# dsky_md_2_1v.net
KiCad netlist of a schematic drawn in EAGLE
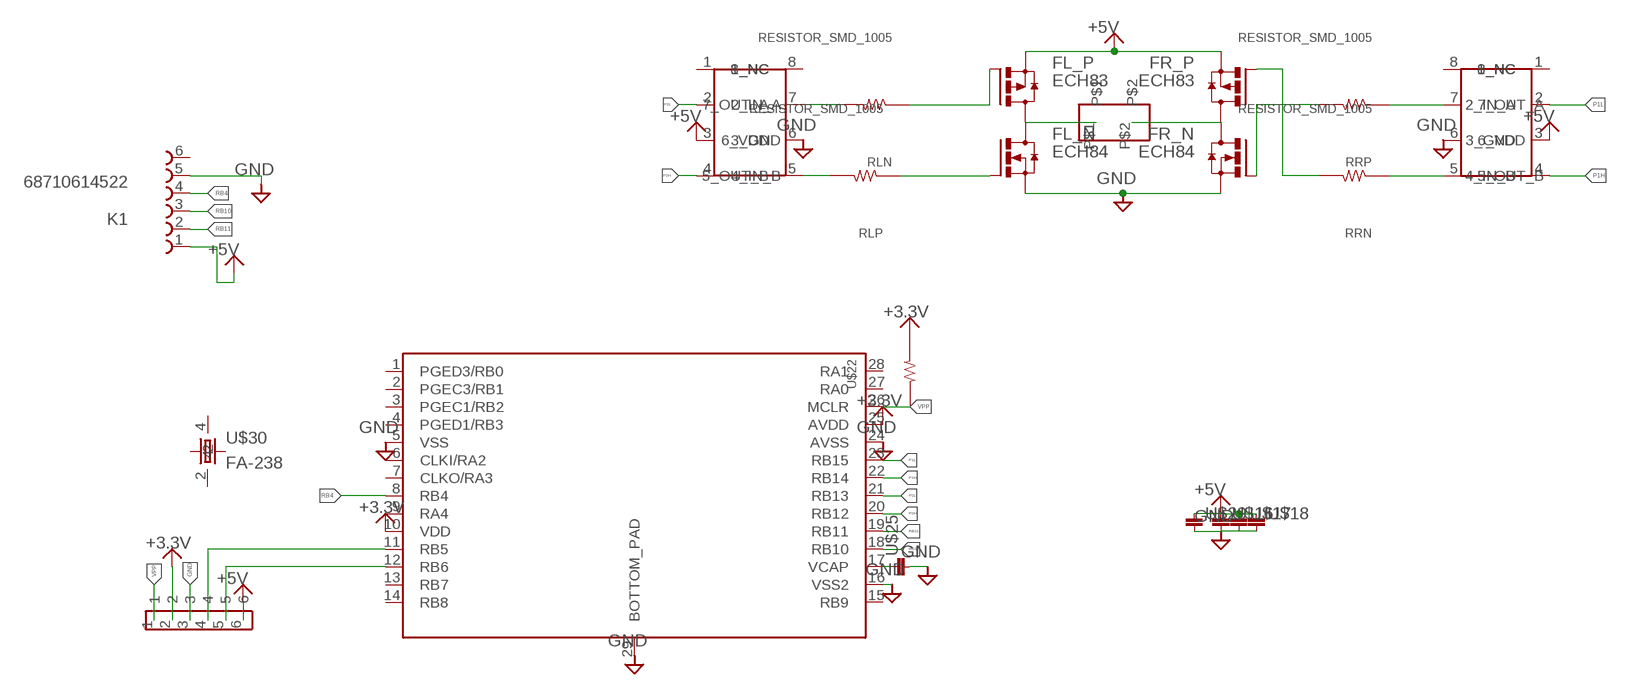
[diagram p0: schematic, sheet 1]

(export (version "E")
  (design (tool "Eeschema 10.0.6"))
  (components
    (comp (ref "FL_N")
      (value "ECH84")
      (footprint "eagle-import:ECH8")
      (libsource (lib "eagle-import") (part "ECH84"))
    )
    (comp (ref "FL_P")
      (value "ECH83")
      (footprint "eagle-import:ECH8")
      (libsource (lib "eagle-import") (part "ECH83"))
    )
    (comp (ref "FR_N")
      (value "ECH84")
      (footprint "eagle-import:ECH8")
      (libsource (lib "eagle-import") (part "ECH84"))
    )
    (comp (ref "FR_P")
      (value "ECH83")
      (footprint "eagle-import:ECH8")
      (libsource (lib "eagle-import") (part "ECH83"))
    )
    (comp (ref "IC_L")
      (value "TC1427COA")
      (footprint "eagle-import:SOIC8")
      (libsource (lib "eagle-import") (part "TC1427COA"))
    )
    (comp (ref "IC_R")
      (value "TC1427COA")
      (footprint "eagle-import:SOIC8")
      (libsource (lib "eagle-import") (part "TC1427COA"))
    )
    (comp (ref "K1")
      (value "68710614522")
      (footprint "eagle-import:68710614522")
      (libsource (lib "eagle-import") (part "68710614522"))
    )
    (comp (ref "RLN")
      (value "RESISTOR_SMD_1005")
      (footprint "eagle-import:1005")
      (libsource (lib "eagle-import") (part "RESISTOR_SMD_1005"))
    )
    (comp (ref "RLP")
      (value "RESISTOR_SMD_1005")
      (footprint "eagle-import:1005")
      (libsource (lib "eagle-import") (part "RESISTOR_SMD_1005"))
    )
    (comp (ref "RRN")
      (value "RESISTOR_SMD_1005")
      (footprint "eagle-import:1005")
      (libsource (lib "eagle-import") (part "RESISTOR_SMD_1005"))
    )
    (comp (ref "RRP")
      (value "RESISTOR_SMD_1005")
      (footprint "eagle-import:1005")
      (libsource (lib "eagle-import") (part "RESISTOR_SMD_1005"))
    )
    (comp (ref "U$3")
      (value "PIN_HEADER_2")
      (footprint "eagle-import:PIN_HEADER_2S")
      (libsource (lib "eagle-import") (part "PIN_HEADER_2"))
    )
    (comp (ref "U$5")
      (value "DSPIC33EP32MC202")
      (footprint "eagle-import:QFN-S28_6X6MC")
      (libsource (lib "eagle-import") (part "DSPIC33EP32MC202"))
    )
    (comp (ref "U$6")
      (value "PIN_HEADER_HALF_6")
      (footprint "eagle-import:PIN_HEADER_HALF_6")
      (libsource (lib "eagle-import") (part "PIN_HEADER_HALF_6"))
    )
    (comp (ref "U$16")
      (value "1608")
      (footprint "eagle-import:1608")
      (libsource (lib "eagle-import") (part "1608"))
    )
    (comp (ref "U$17")
      (value "1608")
      (footprint "eagle-import:1608")
      (libsource (lib "eagle-import") (part "1608"))
    )
    (comp (ref "U$18")
      (value "1608")
      (footprint "eagle-import:1608")
      (libsource (lib "eagle-import") (part "1608"))
    )
    (comp (ref "U$22")
      (value "RESISTOR__SMD")
      (footprint "eagle-import:1608")
      (libsource (lib "eagle-import") (part "RESISTOR__SMD"))
    )
    (comp (ref "U$25")
      (value "1608")
      (footprint "eagle-import:1608")
      (libsource (lib "eagle-import") (part "1608"))
    )
    (comp (ref "U$29")
      (value "2012")
      (footprint "eagle-import:2012")
      (libsource (lib "eagle-import") (part "2012"))
    )
    (comp (ref "U$30")
      (value "FA-238")
      (footprint "eagle-import:FA-238")
      (libsource (lib "eagle-import") (part "FA-238"))
    )
  )
  (nets
    (net (code "1") (name "+3.3V") (class "Default")
      (node (ref "U$22") (pin "2") (pinfunction "P$2_2") (pintype "passive"))
      (node (ref "U$5") (pin "10") (pinfunction "VDD_10") (pintype "bidirectional"))
      (node (ref "U$5") (pin "25") (pinfunction "AVDD_25") (pintype "bidirectional"))
      (node (ref "U$6") (pin "2") (pinfunction "2_2") (pintype "bidirectional"))
    )
    (net (code "2") (name "+5V") (class "Default")
      (node (ref "FL_P") (pin "1") (pinfunction "S_1") (pintype "passive"))
      (node (ref "FL_P") (pin "2") (pinfunction "S_2") (pintype "passive"))
      (node (ref "FL_P") (pin "3") (pinfunction "S_3") (pintype "passive"))
      (node (ref "FR_P") (pin "1") (pinfunction "S_1") (pintype "passive"))
      (node (ref "FR_P") (pin "2") (pinfunction "S_2") (pintype "passive"))
      (node (ref "FR_P") (pin "3") (pinfunction "S_3") (pintype "passive"))
      (node (ref "IC_L") (pin "3") (pinfunction "3_GND_3") (pintype "bidirectional"))
      (node (ref "IC_R") (pin "3") (pinfunction "3_GND_3") (pintype "bidirectional"))
      (node (ref "K1") (pin "1") (pinfunction "1_1") (pintype "passive"))
      (node (ref "U$16") (pin "P$1") (pinfunction "1_P$1") (pintype "passive"))
      (node (ref "U$17") (pin "P$1") (pinfunction "1_P$1") (pintype "passive"))
      (node (ref "U$18") (pin "P$1") (pinfunction "1_P$1") (pintype "passive"))
      (node (ref "U$29") (pin "1") (pinfunction "1_1") (pintype "passive"))
      (node (ref "U$6") (pin "6") (pinfunction "6_6") (pintype "bidirectional"))
    )
    (net (code "3") (name "GND") (class "Default")
      (node (ref "FL_N") (pin "1") (pinfunction "S_1") (pintype "passive"))
      (node (ref "FL_N") (pin "2") (pinfunction "S_2") (pintype "passive"))
      (node (ref "FL_N") (pin "3") (pinfunction "S_3") (pintype "passive"))
      (node (ref "FR_N") (pin "1") (pinfunction "S_1") (pintype "passive"))
      (node (ref "FR_N") (pin "2") (pinfunction "S_2") (pintype "passive"))
      (node (ref "FR_N") (pin "3") (pinfunction "S_3") (pintype "passive"))
      (node (ref "IC_L") (pin "6") (pinfunction "6_VDD_6") (pintype "bidirectional"))
      (node (ref "IC_R") (pin "6") (pinfunction "6_VDD_6") (pintype "bidirectional"))
      (node (ref "K1") (pin "5") (pinfunction "5_5") (pintype "passive"))
      (node (ref "U$16") (pin "P$2") (pinfunction "2_P$2") (pintype "passive"))
      (node (ref "U$17") (pin "P$2") (pinfunction "2_P$2") (pintype "passive"))
      (node (ref "U$18") (pin "P$2") (pinfunction "2_P$2") (pintype "passive"))
      (node (ref "U$25") (pin "P$2") (pinfunction "2_P$2") (pintype "passive"))
      (node (ref "U$29") (pin "2") (pinfunction "2_2") (pintype "passive"))
      (node (ref "U$5") (pin "16") (pinfunction "VSS2_16") (pintype "power_in"))
      (node (ref "U$5") (pin "24") (pinfunction "AVSS_24") (pintype "bidirectional"))
      (node (ref "U$5") (pin "29") (pinfunction "BOTTOM_PAD_29") (pintype "bidirectional"))
      (node (ref "U$5") (pin "5") (pinfunction "VSS_5") (pintype "power_in"))
      (node (ref "U$6") (pin "3") (pinfunction "3_3") (pintype "bidirectional"))
    )
    (net (code "4") (name "Net-(FL_N-D-Pad5)") (class "Default")
      (node (ref "FL_N") (pin "5") (pinfunction "D_5") (pintype "passive"))
      (node (ref "FL_N") (pin "6") (pinfunction "D_6") (pintype "passive"))
      (node (ref "FL_N") (pin "7") (pinfunction "D_7") (pintype "passive"))
      (node (ref "FL_N") (pin "8") (pinfunction "D_8") (pintype "passive"))
      (node (ref "FL_P") (pin "5") (pinfunction "D_5") (pintype "passive"))
      (node (ref "FL_P") (pin "6") (pinfunction "D_6") (pintype "passive"))
      (node (ref "FL_P") (pin "7") (pinfunction "D_7") (pintype "passive"))
      (node (ref "FL_P") (pin "8") (pinfunction "D_8") (pintype "passive"))
      (node (ref "U$3") (pin "P$1") (pinfunction "P$1_P$1") (pintype "bidirectional"))
    )
    (net (code "5") (name "Net-(FL_N-G)") (class "Default")
      (node (ref "FL_N") (pin "4") (pinfunction "G_4") (pintype "passive"))
      (node (ref "RLP") (pin "1") (pinfunction "P$1_1") (pintype "passive"))
    )
    (net (code "6") (name "Net-(FL_P-G)") (class "Default")
      (node (ref "FL_P") (pin "4") (pinfunction "G_4") (pintype "passive"))
      (node (ref "RLN") (pin "1") (pinfunction "P$1_1") (pintype "passive"))
    )
    (net (code "7") (name "Net-(FR_N-D-Pad5)") (class "Default")
      (node (ref "FR_N") (pin "5") (pinfunction "D_5") (pintype "passive"))
      (node (ref "FR_N") (pin "6") (pinfunction "D_6") (pintype "passive"))
      (node (ref "FR_N") (pin "7") (pinfunction "D_7") (pintype "passive"))
      (node (ref "FR_N") (pin "8") (pinfunction "D_8") (pintype "passive"))
      (node (ref "FR_P") (pin "5") (pinfunction "D_5") (pintype "passive"))
      (node (ref "FR_P") (pin "6") (pinfunction "D_6") (pintype "passive"))
      (node (ref "FR_P") (pin "7") (pinfunction "D_7") (pintype "passive"))
      (node (ref "FR_P") (pin "8") (pinfunction "D_8") (pintype "passive"))
      (node (ref "U$3") (pin "P$2") (pinfunction "P$2_P$2") (pintype "bidirectional"))
    )
    (net (code "8") (name "Net-(FR_N-G)") (class "Default")
      (node (ref "FR_N") (pin "4") (pinfunction "G_4") (pintype "passive"))
      (node (ref "RRP") (pin "2") (pinfunction "P$2_2") (pintype "passive"))
    )
    (net (code "9") (name "Net-(FR_P-G)") (class "Default")
      (node (ref "FR_P") (pin "4") (pinfunction "G_4") (pintype "passive"))
      (node (ref "RRN") (pin "2") (pinfunction "P$2_2") (pintype "passive"))
    )
    (net (code "10") (name "Net-(IC_L-5_OUT_B)") (class "Default")
      (node (ref "IC_L") (pin "5") (pinfunction "5_OUT_B_5") (pintype "bidirectional"))
      (node (ref "RLP") (pin "2") (pinfunction "P$2_2") (pintype "passive"))
    )
    (net (code "11") (name "Net-(IC_L-7_OUT_A)") (class "Default")
      (node (ref "IC_L") (pin "7") (pinfunction "7_OUT_A_7") (pintype "bidirectional"))
      (node (ref "RLN") (pin "2") (pinfunction "P$2_2") (pintype "passive"))
    )
    (net (code "12") (name "Net-(IC_R-5_OUT_B)") (class "Default")
      (node (ref "IC_R") (pin "5") (pinfunction "5_OUT_B_5") (pintype "bidirectional"))
      (node (ref "RRN") (pin "1") (pinfunction "P$1_1") (pintype "passive"))
    )
    (net (code "13") (name "Net-(IC_R-7_OUT_A)") (class "Default")
      (node (ref "IC_R") (pin "7") (pinfunction "7_OUT_A_7") (pintype "bidirectional"))
      (node (ref "RRP") (pin "1") (pinfunction "P$1_1") (pintype "passive"))
    )
    (net (code "14") (name "Net-(U$5-RB5)") (class "Default")
      (node (ref "U$5") (pin "11") (pinfunction "RB5_11") (pintype "bidirectional"))
      (node (ref "U$6") (pin "4") (pinfunction "4_4") (pintype "bidirectional"))
    )
    (net (code "15") (name "Net-(U$5-RB6)") (class "Default")
      (node (ref "U$5") (pin "12") (pinfunction "RB6_12") (pintype "bidirectional"))
      (node (ref "U$6") (pin "5") (pinfunction "5_5") (pintype "bidirectional"))
    )
    (net (code "16") (name "Net-(U$25-1)") (class "Default")
      (node (ref "U$25") (pin "P$1") (pinfunction "1_P$1") (pintype "passive"))
      (node (ref "U$5") (pin "17") (pinfunction "VCAP_17") (pintype "bidirectional"))
    )
    (net (code "17") (name "P1H") (class "Default")
      (node (ref "IC_R") (pin "4") (pinfunction "4_IN_B_4") (pintype "bidirectional"))
      (node (ref "U$5") (pin "22") (pinfunction "RB14_22") (pintype "bidirectional"))
    )
    (net (code "18") (name "P1L") (class "Default")
      (node (ref "IC_R") (pin "2") (pinfunction "2_IN_A_2") (pintype "bidirectional"))
      (node (ref "U$5") (pin "23") (pinfunction "RB15_23") (pintype "bidirectional"))
    )
    (net (code "19") (name "P2H") (class "Default")
      (node (ref "IC_L") (pin "4") (pinfunction "4_IN_B_4") (pintype "bidirectional"))
      (node (ref "U$5") (pin "20") (pinfunction "RB12_20") (pintype "bidirectional"))
    )
    (net (code "20") (name "P2L") (class "Default")
      (node (ref "IC_L") (pin "2") (pinfunction "2_IN_A_2") (pintype "bidirectional"))
      (node (ref "U$5") (pin "21") (pinfunction "RB13_21") (pintype "bidirectional"))
    )
    (net (code "21") (name "RB4") (class "Default")
      (node (ref "K1") (pin "4") (pinfunction "4_4") (pintype "passive"))
      (node (ref "U$5") (pin "8") (pinfunction "RB4_8") (pintype "bidirectional"))
    )
    (net (code "22") (name "RB10") (class "Default")
      (node (ref "K1") (pin "3") (pinfunction "3_3") (pintype "passive"))
      (node (ref "U$5") (pin "18") (pinfunction "RB10_18") (pintype "bidirectional"))
    )
    (net (code "23") (name "RB11") (class "Default")
      (node (ref "K1") (pin "2") (pinfunction "2_2") (pintype "passive"))
      (node (ref "U$5") (pin "19") (pinfunction "RB11_19") (pintype "bidirectional"))
    )
    (net (code "24") (name "VPP") (class "Default")
      (node (ref "U$22") (pin "1") (pinfunction "P$1_1") (pintype "passive"))
      (node (ref "U$5") (pin "26") (pinfunction "MCLR_26") (pintype "bidirectional"))
      (node (ref "U$6") (pin "1") (pinfunction "1_1") (pintype "bidirectional"))
    )
    (net (code "25") (name "unconnected-(IC_L-1_NC-Pad1)") (class "Default")
      (node (ref "IC_L") (pin "1") (pinfunction "1_NC_1") (pintype "bidirectional"))
    )
    (net (code "26") (name "unconnected-(IC_L-8_NC-Pad8)") (class "Default")
      (node (ref "IC_L") (pin "8") (pinfunction "8_NC_8") (pintype "bidirectional"))
    )
    (net (code "27") (name "unconnected-(IC_R-1_NC-Pad1)") (class "Default")
      (node (ref "IC_R") (pin "1") (pinfunction "1_NC_1") (pintype "bidirectional"))
    )
    (net (code "28") (name "unconnected-(IC_R-8_NC-Pad8)") (class "Default")
      (node (ref "IC_R") (pin "8") (pinfunction "8_NC_8") (pintype "bidirectional"))
    )
    (net (code "29") (name "unconnected-(K1-Pad6)") (class "Default")
      (node (ref "K1") (pin "6") (pinfunction "6_6") (pintype "passive"))
    )
    (net (code "30") (name "unconnected-(U$5-CLKI{slash}RA2-Pad6)") (class "Default")
      (node (ref "U$5") (pin "6") (pinfunction "CLKI/RA2_6") (pintype "bidirectional"))
    )
    (net (code "31") (name "unconnected-(U$5-CLKO{slash}RA3-Pad7)") (class "Default")
      (node (ref "U$5") (pin "7") (pinfunction "CLKO/RA3_7") (pintype "bidirectional"))
    )
    (net (code "32") (name "unconnected-(U$5-PGEC1{slash}RB2-Pad3)") (class "Default")
      (node (ref "U$5") (pin "3") (pinfunction "PGEC1/RB2_3") (pintype "bidirectional"))
    )
    (net (code "33") (name "unconnected-(U$5-PGEC3{slash}RB1-Pad2)") (class "Default")
      (node (ref "U$5") (pin "2") (pinfunction "PGEC3/RB1_2") (pintype "bidirectional"))
    )
    (net (code "34") (name "unconnected-(U$5-PGED1{slash}RB3-Pad4)") (class "Default")
      (node (ref "U$5") (pin "4") (pinfunction "PGED1/RB3_4") (pintype "bidirectional"))
    )
    (net (code "35") (name "unconnected-(U$5-PGED3{slash}RB0-Pad1)") (class "Default")
      (node (ref "U$5") (pin "1") (pinfunction "PGED3/RB0_1") (pintype "bidirectional"))
    )
    (net (code "36") (name "unconnected-(U$5-RA0-Pad27)") (class "Default")
      (node (ref "U$5") (pin "27") (pinfunction "RA0_27") (pintype "bidirectional"))
    )
    (net (code "37") (name "unconnected-(U$5-RA1-Pad28)") (class "Default")
      (node (ref "U$5") (pin "28") (pinfunction "RA1_28") (pintype "bidirectional"))
    )
    (net (code "38") (name "unconnected-(U$5-RA4-Pad9)") (class "Default")
      (node (ref "U$5") (pin "9") (pinfunction "RA4_9") (pintype "bidirectional"))
    )
    (net (code "39") (name "unconnected-(U$5-RB7-Pad13)") (class "Default")
      (node (ref "U$5") (pin "13") (pinfunction "RB7_13") (pintype "bidirectional"))
    )
    (net (code "40") (name "unconnected-(U$5-RB8-Pad14)") (class "Default")
      (node (ref "U$5") (pin "14") (pinfunction "RB8_14") (pintype "bidirectional"))
    )
    (net (code "41") (name "unconnected-(U$5-RB9-Pad15)") (class "Default")
      (node (ref "U$5") (pin "15") (pinfunction "RB9_15") (pintype "bidirectional"))
    )
    (net (code "42") (name "unconnected-(U$30-Pad1)") (class "Default")
      (node (ref "U$30") (pin "1") (pinfunction "1_1") (pintype "passive"))
    )
    (net (code "43") (name "unconnected-(U$30-Pad2)") (class "Default")
      (node (ref "U$30") (pin "2") (pinfunction "2_2") (pintype "bidirectional"))
    )
    (net (code "44") (name "unconnected-(U$30-Pad3)") (class "Default")
      (node (ref "U$30") (pin "3") (pinfunction "3_3") (pintype "passive"))
    )
    (net (code "45") (name "unconnected-(U$30-Pad4)") (class "Default")
      (node (ref "U$30") (pin "4") (pinfunction "4_4") (pintype "bidirectional"))
    )
  )
)
